# pc_afe44xx_shield_v2.net
KiCad netlist of a schematic drawn in EAGLE
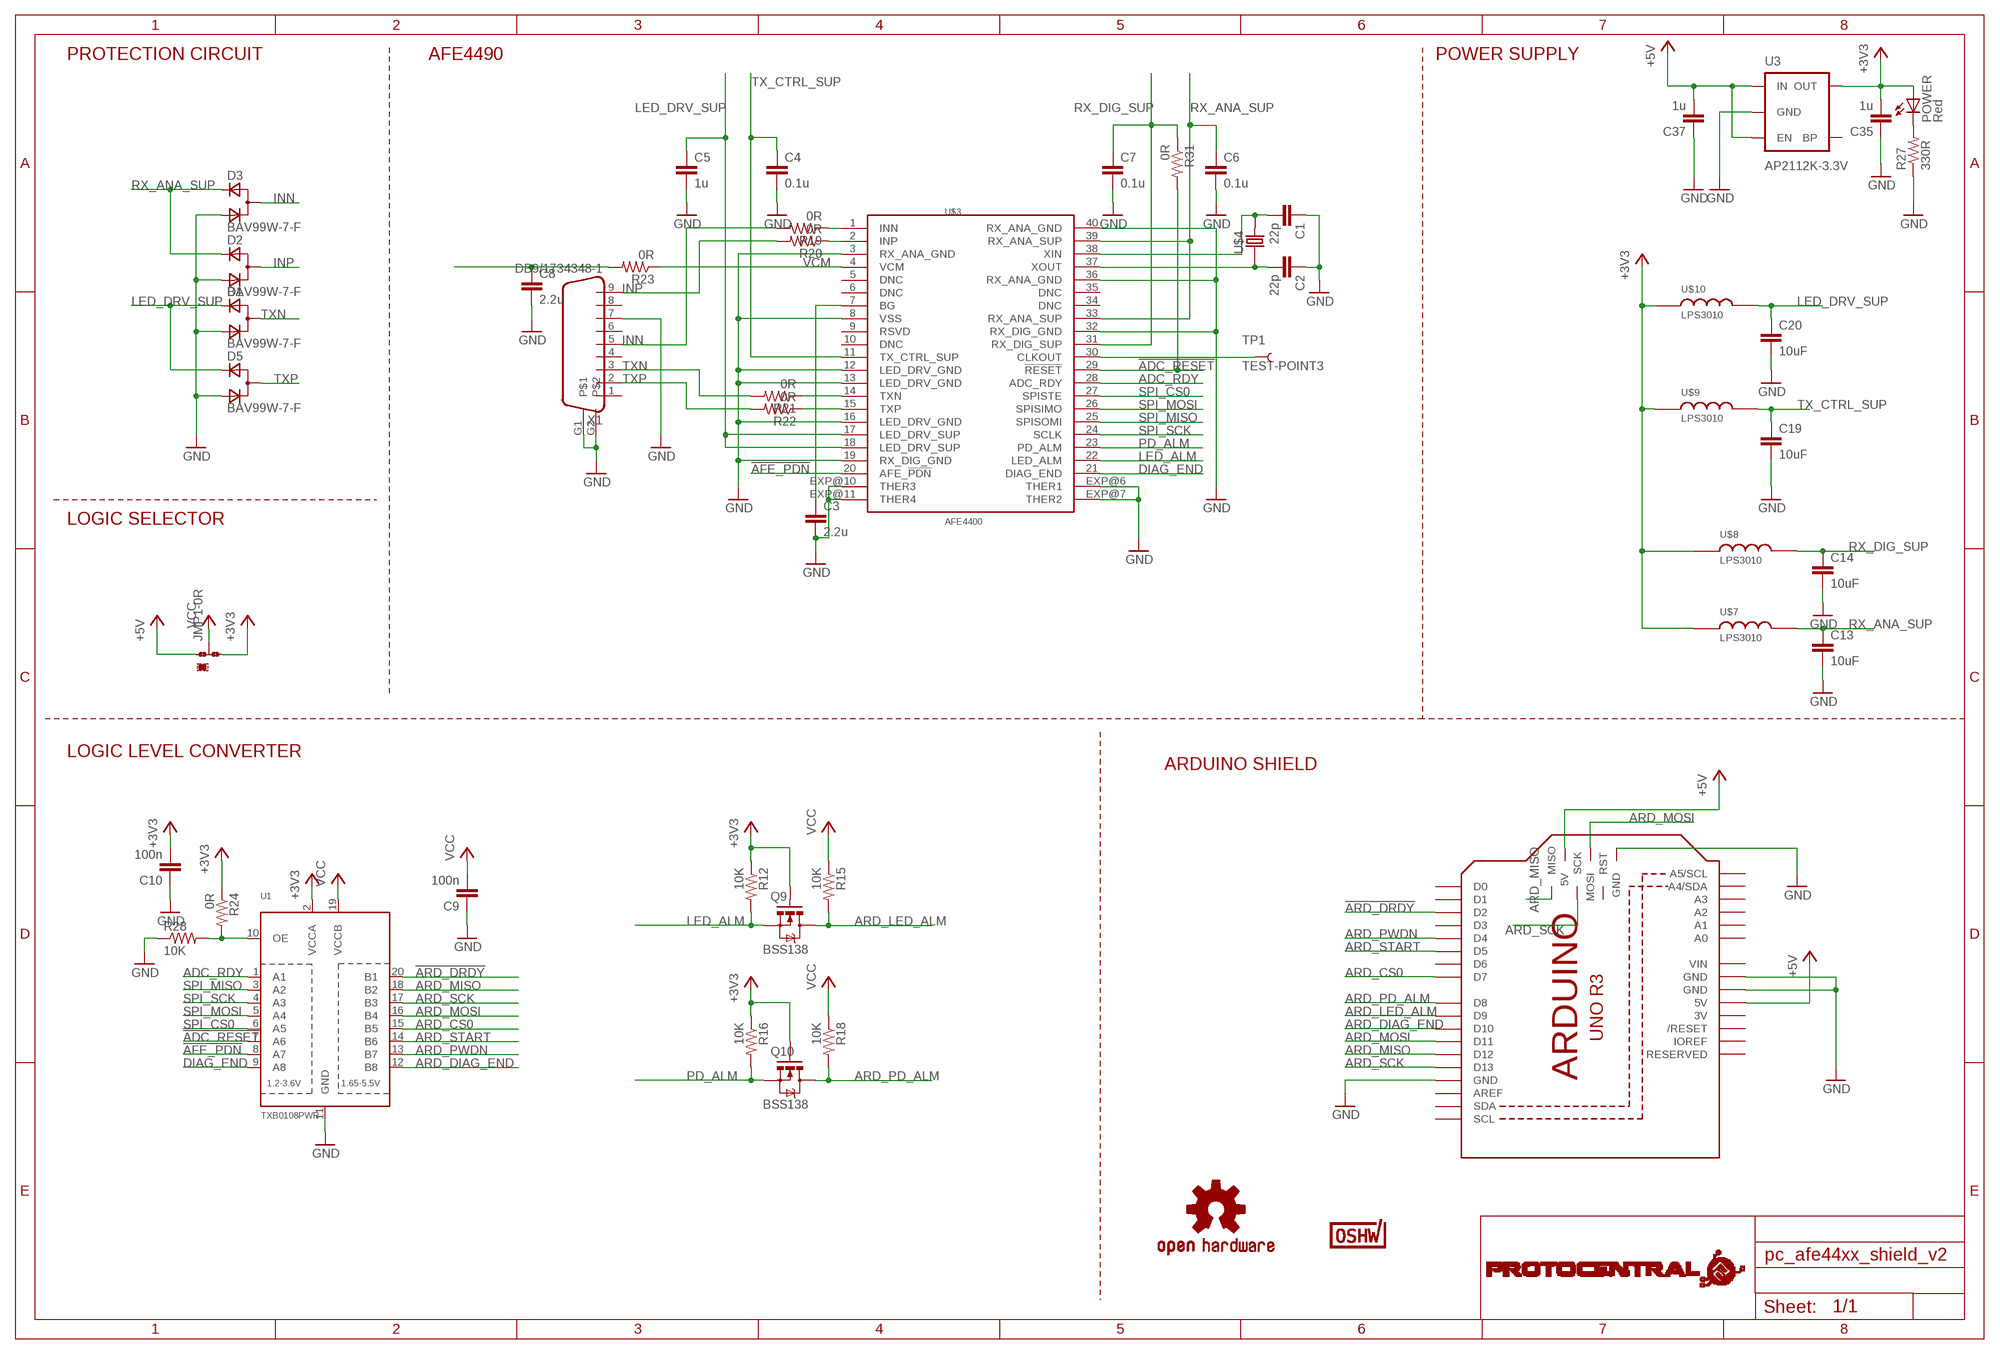
[diagram p0: schematic, sheet 1]

(export (version "E")
  (design (tool "Eeschema 10.0.6"))
  (components
    (comp (ref "C1")
      (value "22p")
      (footprint "eagle-import:C0402")
      (libsource (lib "eagle-import") (part "C-EUC0402"))
    )
    (comp (ref "C2")
      (value "22p")
      (footprint "eagle-import:C0402")
      (libsource (lib "eagle-import") (part "C-EUC0402"))
    )
    (comp (ref "C3")
      (value "2.2u")
      (footprint "eagle-import:C0402")
      (libsource (lib "eagle-import") (part "C-EUC0402"))
    )
    (comp (ref "C4")
      (value "0.1u")
      (footprint "eagle-import:C0805")
      (libsource (lib "eagle-import") (part "C-EUC0805"))
    )
    (comp (ref "C5")
      (value "1u")
      (footprint "eagle-import:C0805")
      (libsource (lib "eagle-import") (part "C-EUC0805"))
    )
    (comp (ref "C6")
      (value "0.1u")
      (footprint "eagle-import:C0805")
      (libsource (lib "eagle-import") (part "C-EUC0805"))
    )
    (comp (ref "C7")
      (value "0.1u")
      (footprint "eagle-import:C0805")
      (libsource (lib "eagle-import") (part "C-EUC0805"))
    )
    (comp (ref "C8")
      (value "2.2u")
      (footprint "eagle-import:C0402")
      (libsource (lib "eagle-import") (part "C-EUC0402"))
    )
    (comp (ref "C9")
      (value "100n")
      (footprint "eagle-import:C0402")
      (libsource (lib "eagle-import") (part "C-EUC0402"))
    )
    (comp (ref "C10")
      (value "100n")
      (footprint "eagle-import:C0402")
      (libsource (lib "eagle-import") (part "C-EUC0402"))
    )
    (comp (ref "C13")
      (value "10uF")
      (footprint "eagle-import:C0805")
      (libsource (lib "eagle-import") (part "C-EUC0805"))
    )
    (comp (ref "C14")
      (value "10uF")
      (footprint "eagle-import:C0805")
      (libsource (lib "eagle-import") (part "C-EUC0805"))
    )
    (comp (ref "C19")
      (value "10uF")
      (footprint "eagle-import:C0805")
      (libsource (lib "eagle-import") (part "C-EUC0805"))
    )
    (comp (ref "C20")
      (value "10uF")
      (footprint "eagle-import:C0805")
      (libsource (lib "eagle-import") (part "C-EUC0805"))
    )
    (comp (ref "C35")
      (value "1u")
      (footprint "eagle-import:C0805")
      (libsource (lib "eagle-import") (part "C-EUC0805"))
    )
    (comp (ref "C37")
      (value "1u")
      (footprint "eagle-import:C0805")
      (libsource (lib "eagle-import") (part "C-EUC0805"))
    )
    (comp (ref "D1")
      (value "BAV99W-7-F")
      (footprint "eagle-import:SOT323")
      (libsource (lib "eagle-import") (part "D_ACACSOT323"))
    )
    (comp (ref "D2")
      (value "BAV99W-7-F")
      (footprint "eagle-import:SOT323")
      (libsource (lib "eagle-import") (part "D_ACACSOT323"))
    )
    (comp (ref "D3")
      (value "BAV99W-7-F")
      (footprint "eagle-import:SOT323")
      (libsource (lib "eagle-import") (part "D_ACACSOT323"))
    )
    (comp (ref "D5")
      (value "BAV99W-7-F")
      (footprint "eagle-import:SOT323")
      (libsource (lib "eagle-import") (part "D_ACACSOT323"))
    )
    (comp (ref "JMP1")
      (value "0R-JUMPA")
      (footprint "eagle-import:A0R-JMP")
      (libsource (lib "eagle-import") (part "0R-JUMPA"))
    )
    (comp (ref "M1")
      (value "ARDUINO")
      (footprint "eagle-import:ARDUINO")
      (libsource (lib "eagle-import") (part "ARDUINO"))
    )
    (comp (ref "POWER")
      (value "Red")
      (footprint "eagle-import:CHIPLED_0603")
      (libsource (lib "eagle-import") (part "LEDCHIPLED_0603"))
    )
    (comp (ref "Q9")
      (value "BSS138")
      (footprint "eagle-import:SOT23-3")
      (libsource (lib "eagle-import") (part "MOSFET-NCHANNELSMD"))
    )
    (comp (ref "Q10")
      (value "BSS138")
      (footprint "eagle-import:SOT23-3")
      (libsource (lib "eagle-import") (part "MOSFET-NCHANNELSMD"))
    )
    (comp (ref "R12")
      (value "10K")
      (footprint "eagle-import:0805")
      (libsource (lib "eagle-import") (part "RESISTOR0805-RES"))
    )
    (comp (ref "R15")
      (value "10K")
      (footprint "eagle-import:0805")
      (libsource (lib "eagle-import") (part "RESISTOR0805-RES"))
    )
    (comp (ref "R16")
      (value "10K")
      (footprint "eagle-import:0805")
      (libsource (lib "eagle-import") (part "RESISTOR0805-RES"))
    )
    (comp (ref "R18")
      (value "10K")
      (footprint "eagle-import:0805")
      (libsource (lib "eagle-import") (part "RESISTOR0805-RES"))
    )
    (comp (ref "R19")
      (value "0R")
      (footprint "eagle-import:R0402")
      (libsource (lib "eagle-import") (part "R-US_R0402"))
    )
    (comp (ref "R20")
      (value "0R")
      (footprint "eagle-import:R0402")
      (libsource (lib "eagle-import") (part "R-US_R0402"))
    )
    (comp (ref "R21")
      (value "0R")
      (footprint "eagle-import:R0805")
      (libsource (lib "eagle-import") (part "R-US_R0805"))
    )
    (comp (ref "R22")
      (value "0R")
      (footprint "eagle-import:R0805")
      (libsource (lib "eagle-import") (part "R-US_R0805"))
    )
    (comp (ref "R23")
      (value "0R")
      (footprint "eagle-import:R0402")
      (libsource (lib "eagle-import") (part "R-US_R0402"))
    )
    (comp (ref "R24")
      (value "0R")
      (footprint "eagle-import:0805")
      (libsource (lib "eagle-import") (part "RESISTOR0805-RES"))
    )
    (comp (ref "R27")
      (value "330R")
      (footprint "eagle-import:R0805")
      (libsource (lib "eagle-import") (part "R-US_R0805"))
    )
    (comp (ref "R28")
      (value "10K")
      (footprint "eagle-import:0805")
      (libsource (lib "eagle-import") (part "RESISTOR0805-RES"))
    )
    (comp (ref "R31")
      (value "0R")
      (footprint "eagle-import:R0805")
      (libsource (lib "eagle-import") (part "R-US_R0805"))
    )
    (comp (ref "TP1")
      (value "TEST-POINT3")
      (footprint "eagle-import:PAD.03X.03")
      (libsource (lib "eagle-import") (part "TEST-POINT3"))
    )
    (comp (ref "U$3")
      (value "AFE4400")
      (footprint "eagle-import:QFN-40")
      (libsource (lib "eagle-import") (part "AFE4400"))
    )
    (comp (ref "U$4")
      (value "ABM3")
      (footprint "eagle-import:ABM3")
      (libsource (lib "eagle-import") (part "ABM3"))
    )
    (comp (ref "U$5")
      (value "PROTY_LOGO_WITH_TEXT")
      (footprint "eagle-import:PROTY_WITH_TEXT")
      (libsource (lib "eagle-import") (part "PROTY_LOGO_WITH_TEXT"))
    )
    (comp (ref "U$6")
      (value "CERT-SMALL")
      (footprint "eagle-import:CERT-SMALL-SILK")
      (libsource (lib "eagle-import") (part "CERT-SMALL"))
    )
    (comp (ref "U$7")
      (value "LPS3010")
      (footprint "eagle-import:LPS")
      (libsource (lib "eagle-import") (part "LPS"))
    )
    (comp (ref "U$8")
      (value "LPS3010")
      (footprint "eagle-import:LPS")
      (libsource (lib "eagle-import") (part "LPS"))
    )
    (comp (ref "U$9")
      (value "LPS3010")
      (footprint "eagle-import:LPS")
      (libsource (lib "eagle-import") (part "LPS"))
    )
    (comp (ref "U$10")
      (value "LPS3010")
      (footprint "eagle-import:LPS")
      (libsource (lib "eagle-import") (part "LPS"))
    )
    (comp (ref "U$11")
      (value "OSHW-LOGOM")
      (footprint "eagle-import:OSHW-LOGO-M")
      (libsource (lib "eagle-import") (part "OSHW-LOGOM"))
    )
    (comp (ref "U1")
      (value "TXB0108PWR")
      (footprint "eagle-import:TSSOP20")
      (libsource (lib "eagle-import") (part "TXB0108PWR"))
    )
    (comp (ref "U3")
      (value "AP2112K-3.3V")
      (footprint "eagle-import:SOT23-5")
      (libsource (lib "eagle-import") (part "V_REG_LDOSMD"))
    )
    (comp (ref "X1")
      (value "DB9/1734348-1")
      (footprint "eagle-import:DB9")
      (libsource (lib "eagle-import") (part "DB9"))
    )
  )
  (nets
    (net (code "1") (name "+3V3") (class "Default")
      (node (ref "C10") (pin "2") (pinfunction "2_2") (pintype "passive"))
      (node (ref "C35") (pin "2") (pinfunction "2_2") (pintype "passive"))
      (node (ref "JMP1") (pin "3") (pinfunction "3_3") (pintype "passive"))
      (node (ref "POWER") (pin "A") (pinfunction "A_A") (pintype "passive"))
      (node (ref "Q10") (pin "1") (pinfunction "G_1") (pintype "passive"))
      (node (ref "Q9") (pin "1") (pinfunction "G_1") (pintype "passive"))
      (node (ref "R12") (pin "1") (pinfunction "1_1") (pintype "passive"))
      (node (ref "R16") (pin "1") (pinfunction "1_1") (pintype "passive"))
      (node (ref "R24") (pin "1") (pinfunction "1_1") (pintype "passive"))
      (node (ref "U$10") (pin "1") (pinfunction "P$1_1") (pintype "bidirectional"))
      (node (ref "U$7") (pin "1") (pinfunction "P$1_1") (pintype "bidirectional"))
      (node (ref "U$8") (pin "1") (pinfunction "P$1_1") (pintype "bidirectional"))
      (node (ref "U$9") (pin "1") (pinfunction "P$1_1") (pintype "bidirectional"))
      (node (ref "U1") (pin "2") (pinfunction "VCCA_2") (pintype "bidirectional"))
      (node (ref "U3") (pin "5") (pinfunction "OUT_5") (pintype "passive"))
    )
    (net (code "2") (name "+5V") (class "Default")
      (node (ref "C37") (pin "2") (pinfunction "2_2") (pintype "passive"))
      (node (ref "JMP1") (pin "1") (pinfunction "1_1") (pintype "passive"))
      (node (ref "M1") (pin "5V") (pinfunction "5V_5V") (pintype "power_in"))
      (node (ref "M1") (pin "5V_ICSP") (pinfunction "5V_5V_ICSP") (pintype "passive"))
      (node (ref "U3") (pin "1") (pinfunction "IN_1") (pintype "input"))
      (node (ref "U3") (pin "3") (pinfunction "EN_3") (pintype "input"))
    )
    (net (code "3") (name "/3V") (class "Default")
      (node (ref "M1") (pin "3V") (pinfunction "3V_3V") (pintype "power_in"))
    )
    (net (code "4") (name "/ADC_RDY") (class "Default")
      (node (ref "U$3") (pin "28") (pinfunction "ADC_RDY_28") (pintype "bidirectional"))
      (node (ref "U1") (pin "1") (pinfunction "A1_1") (pintype "bidirectional"))
    )
    (net (code "5") (name "/ARD_CS0") (class "Default")
      (node (ref "M1") (pin "D7") (pinfunction "D7_D7") (pintype "bidirectional"))
      (node (ref "U1") (pin "15") (pinfunction "B5_15") (pintype "bidirectional"))
    )
    (net (code "6") (name "/ARD_DIAG_END") (class "Default")
      (node (ref "M1") (pin "D10") (pinfunction "D10_D10") (pintype "bidirectional"))
      (node (ref "U1") (pin "12") (pinfunction "B8_12") (pintype "bidirectional"))
    )
    (net (code "7") (name "/ARD_LED_ALM") (class "Default")
      (node (ref "M1") (pin "D9") (pinfunction "D9_D9") (pintype "bidirectional"))
      (node (ref "Q9") (pin "3") (pinfunction "D_3") (pintype "passive"))
      (node (ref "R15") (pin "2") (pinfunction "2_2") (pintype "passive"))
    )
    (net (code "8") (name "/ARD_MISO") (class "Default")
      (node (ref "M1") (pin "D12") (pinfunction "D12_D12") (pintype "bidirectional"))
      (node (ref "M1") (pin "MISO") (pinfunction "MISO_MISO") (pintype "passive"))
      (node (ref "U1") (pin "18") (pinfunction "B2_18") (pintype "bidirectional"))
    )
    (net (code "9") (name "/ARD_MOSI") (class "Default")
      (node (ref "M1") (pin "D11") (pinfunction "D11_D11") (pintype "bidirectional"))
      (node (ref "M1") (pin "MOSI") (pinfunction "MOSI_MOSI") (pintype "passive"))
      (node (ref "U1") (pin "16") (pinfunction "B4_16") (pintype "bidirectional"))
    )
    (net (code "10") (name "/ARD_PD_ALM") (class "Default")
      (node (ref "M1") (pin "D8") (pinfunction "D8_D8") (pintype "bidirectional"))
      (node (ref "Q10") (pin "3") (pinfunction "D_3") (pintype "passive"))
      (node (ref "R18") (pin "2") (pinfunction "2_2") (pintype "passive"))
    )
    (net (code "11") (name "/ARD_PWDN") (class "Default")
      (node (ref "M1") (pin "D4") (pinfunction "D4_D4") (pintype "bidirectional"))
      (node (ref "U1") (pin "13") (pinfunction "B7_13") (pintype "bidirectional"))
    )
    (net (code "12") (name "/ARD_SCK") (class "Default")
      (node (ref "M1") (pin "D13") (pinfunction "D13_D13") (pintype "bidirectional"))
      (node (ref "M1") (pin "SCK") (pinfunction "SCK_SCK") (pintype "passive"))
      (node (ref "U1") (pin "17") (pinfunction "B3_17") (pintype "bidirectional"))
    )
    (net (code "13") (name "/ARD_START") (class "Default")
      (node (ref "M1") (pin "D5") (pinfunction "D5_D5") (pintype "bidirectional"))
      (node (ref "U1") (pin "14") (pinfunction "B6_14") (pintype "bidirectional"))
    )
    (net (code "14") (name "/DIAG_END") (class "Default")
      (node (ref "U$3") (pin "21") (pinfunction "DIAG_END_21") (pintype "bidirectional"))
      (node (ref "U1") (pin "9") (pinfunction "A8_9") (pintype "bidirectional"))
    )
    (net (code "15") (name "/INN") (class "Default")
      (node (ref "D3") (pin "1") (pinfunction "CA_1") (pintype "passive"))
      (node (ref "R19") (pin "2") (pinfunction "2_2") (pintype "passive"))
      (node (ref "X1") (pin "5") (pinfunction "5_5") (pintype "passive"))
    )
    (net (code "16") (name "/INP") (class "Default")
      (node (ref "D2") (pin "1") (pinfunction "CA_1") (pintype "passive"))
      (node (ref "R20") (pin "2") (pinfunction "2_2") (pintype "passive"))
      (node (ref "X1") (pin "9") (pinfunction "9_9") (pintype "passive"))
    )
    (net (code "17") (name "/LED_ALM") (class "Default")
      (node (ref "Q9") (pin "2") (pinfunction "S_2") (pintype "passive"))
      (node (ref "R12") (pin "2") (pinfunction "2_2") (pintype "passive"))
      (node (ref "U$3") (pin "22") (pinfunction "LED_ALM_22") (pintype "bidirectional"))
    )
    (net (code "18") (name "/LED_DRV_SUP") (class "Default")
      (node (ref "C20") (pin "1") (pinfunction "1_1") (pintype "passive"))
      (node (ref "C5") (pin "1") (pinfunction "1_1") (pintype "passive"))
      (node (ref "D1") (pin "3") (pinfunction "A_3") (pintype "passive"))
      (node (ref "D5") (pin "3") (pinfunction "A_3") (pintype "passive"))
      (node (ref "U$10") (pin "2") (pinfunction "P$2_2") (pintype "bidirectional"))
      (node (ref "U$3") (pin "17") (pinfunction "LED_DRV_SUP_17") (pintype "bidirectional"))
      (node (ref "U$3") (pin "18") (pinfunction "LED_DRV_SUP_18") (pintype "bidirectional"))
    )
    (net (code "19") (name "/PD_ALM") (class "Default")
      (node (ref "Q10") (pin "2") (pinfunction "S_2") (pintype "passive"))
      (node (ref "R16") (pin "2") (pinfunction "2_2") (pintype "passive"))
      (node (ref "U$3") (pin "23") (pinfunction "PD_ALM_23") (pintype "bidirectional"))
    )
    (net (code "20") (name "/RX_ANA_SUP") (class "Default")
      (node (ref "C13") (pin "1") (pinfunction "1_1") (pintype "passive"))
      (node (ref "C6") (pin "1") (pinfunction "1_1") (pintype "passive"))
      (node (ref "D2") (pin "3") (pinfunction "A_3") (pintype "passive"))
      (node (ref "D3") (pin "3") (pinfunction "A_3") (pintype "passive"))
      (node (ref "U$3") (pin "33") (pinfunction "RX_ANA_SUP_33") (pintype "bidirectional"))
      (node (ref "U$3") (pin "39") (pinfunction "RX_ANA_SUP_39") (pintype "bidirectional"))
      (node (ref "U$7") (pin "2") (pinfunction "P$2_2") (pintype "bidirectional"))
    )
    (net (code "21") (name "/RX_DIG_SUP") (class "Default")
      (node (ref "C14") (pin "1") (pinfunction "1_1") (pintype "passive"))
      (node (ref "C7") (pin "1") (pinfunction "1_1") (pintype "passive"))
      (node (ref "R31") (pin "1") (pinfunction "1_1") (pintype "passive"))
      (node (ref "U$3") (pin "31") (pinfunction "RX_DIG_SUP_31") (pintype "bidirectional"))
      (node (ref "U$8") (pin "2") (pinfunction "P$2_2") (pintype "bidirectional"))
    )
    (net (code "22") (name "/SPI_CS0") (class "Default")
      (node (ref "U$3") (pin "27") (pinfunction "SPISTE_27") (pintype "bidirectional"))
      (node (ref "U1") (pin "6") (pinfunction "A5_6") (pintype "bidirectional"))
    )
    (net (code "23") (name "/SPI_MISO") (class "Default")
      (node (ref "U$3") (pin "25") (pinfunction "SPISOMI_25") (pintype "bidirectional"))
      (node (ref "U1") (pin "3") (pinfunction "A2_3") (pintype "bidirectional"))
    )
    (net (code "24") (name "/SPI_MOSI") (class "Default")
      (node (ref "U$3") (pin "26") (pinfunction "SPISIMO_26") (pintype "bidirectional"))
      (node (ref "U1") (pin "5") (pinfunction "A4_5") (pintype "bidirectional"))
    )
    (net (code "25") (name "/SPI_SCK") (class "Default")
      (node (ref "U$3") (pin "24") (pinfunction "SCLK_24") (pintype "bidirectional"))
      (node (ref "U1") (pin "4") (pinfunction "A3_4") (pintype "bidirectional"))
    )
    (net (code "26") (name "/TXN") (class "Default")
      (node (ref "D1") (pin "1") (pinfunction "CA_1") (pintype "passive"))
      (node (ref "R21") (pin "2") (pinfunction "2_2") (pintype "passive"))
      (node (ref "X1") (pin "3") (pinfunction "3_3") (pintype "passive"))
    )
    (net (code "27") (name "/TXP") (class "Default")
      (node (ref "D5") (pin "1") (pinfunction "CA_1") (pintype "passive"))
      (node (ref "R22") (pin "2") (pinfunction "2_2") (pintype "passive"))
      (node (ref "X1") (pin "2") (pinfunction "2_2") (pintype "passive"))
    )
    (net (code "28") (name "/TX_CTRL_SUP") (class "Default")
      (node (ref "C19") (pin "1") (pinfunction "1_1") (pintype "passive"))
      (node (ref "C4") (pin "1") (pinfunction "1_1") (pintype "passive"))
      (node (ref "U$3") (pin "11") (pinfunction "TX_CTRL_SUP_11") (pintype "bidirectional"))
      (node (ref "U$9") (pin "2") (pinfunction "P$2_2") (pintype "bidirectional"))
    )
    (net (code "29") (name "/VCM") (class "Default")
      (node (ref "R23") (pin "1") (pinfunction "1_1") (pintype "passive"))
      (node (ref "U$3") (pin "4") (pinfunction "VCM_4") (pintype "bidirectional"))
    )
    (net (code "30") (name "/VIN") (class "Default")
      (node (ref "M1") (pin "VIN") (pinfunction "VIN_VIN") (pintype "power_in"))
    )
    (net (code "31") (name "/~{ADC_RESET}") (class "Default")
      (node (ref "R31") (pin "2") (pinfunction "2_2") (pintype "passive"))
      (node (ref "U$3") (pin "29") (pinfunction "~{RESET}_29") (pintype "bidirectional"))
      (node (ref "U1") (pin "7") (pinfunction "A6_7") (pintype "bidirectional"))
    )
    (net (code "32") (name "/~{AFE_PDN}") (class "Default")
      (node (ref "U$3") (pin "20") (pinfunction "AFE_~{PDN}_20") (pintype "bidirectional"))
      (node (ref "U1") (pin "8") (pinfunction "A7_8") (pintype "bidirectional"))
    )
    (net (code "33") (name "/~{ARD_DRDY}") (class "Default")
      (node (ref "M1") (pin "D2") (pinfunction "D2_D2") (pintype "bidirectional"))
      (node (ref "U1") (pin "20") (pinfunction "B1_20") (pintype "bidirectional"))
    )
    (net (code "34") (name "GND") (class "Default")
      (node (ref "C1") (pin "1") (pinfunction "1_1") (pintype "passive"))
      (node (ref "C10") (pin "1") (pinfunction "1_1") (pintype "passive"))
      (node (ref "C13") (pin "2") (pinfunction "2_2") (pintype "passive"))
      (node (ref "C14") (pin "2") (pinfunction "2_2") (pintype "passive"))
      (node (ref "C19") (pin "2") (pinfunction "2_2") (pintype "passive"))
      (node (ref "C2") (pin "1") (pinfunction "1_1") (pintype "passive"))
      (node (ref "C20") (pin "2") (pinfunction "2_2") (pintype "passive"))
      (node (ref "C3") (pin "2") (pinfunction "2_2") (pintype "passive"))
      (node (ref "C35") (pin "1") (pinfunction "1_1") (pintype "passive"))
      (node (ref "C37") (pin "1") (pinfunction "1_1") (pintype "passive"))
      (node (ref "C4") (pin "2") (pinfunction "2_2") (pintype "passive"))
      (node (ref "C5") (pin "2") (pinfunction "2_2") (pintype "passive"))
      (node (ref "C6") (pin "2") (pinfunction "2_2") (pintype "passive"))
      (node (ref "C7") (pin "2") (pinfunction "2_2") (pintype "passive"))
      (node (ref "C8") (pin "2") (pinfunction "2_2") (pintype "passive"))
      (node (ref "C9") (pin "1") (pinfunction "1_1") (pintype "passive"))
      (node (ref "D1") (pin "2") (pinfunction "C_2") (pintype "passive"))
      (node (ref "D2") (pin "2") (pinfunction "C_2") (pintype "passive"))
      (node (ref "D3") (pin "2") (pinfunction "C_2") (pintype "passive"))
      (node (ref "D5") (pin "2") (pinfunction "C_2") (pintype "passive"))
      (node (ref "M1") (pin "GND") (pinfunction "GND_GND") (pintype "power_in"))
      (node (ref "M1") (pin "GND@1") (pinfunction "GND_GND@1") (pintype "power_in"))
      (node (ref "M1") (pin "GND@2") (pinfunction "GND_GND@2") (pintype "power_in"))
      (node (ref "M1") (pin "GND@3") (pinfunction "GND_GND@3") (pintype "passive"))
      (node (ref "R27") (pin "1") (pinfunction "1_1") (pintype "passive"))
      (node (ref "R28") (pin "1") (pinfunction "1_1") (pintype "passive"))
      (node (ref "U$3") (pin "12") (pinfunction "LED_DRV_GND_12") (pintype "bidirectional"))
      (node (ref "U$3") (pin "13") (pinfunction "LED_DRV_GND_13") (pintype "bidirectional"))
      (node (ref "U$3") (pin "16") (pinfunction "LED_DRV_GND_16") (pintype "bidirectional"))
      (node (ref "U$3") (pin "19") (pinfunction "RX_DIG_GND_19") (pintype "bidirectional"))
      (node (ref "U$3") (pin "3") (pinfunction "RX_ANA_GND_3") (pintype "bidirectional"))
      (node (ref "U$3") (pin "32") (pinfunction "RX_DIG_GND_32") (pintype "bidirectional"))
      (node (ref "U$3") (pin "36") (pinfunction "RX_ANA_GND_36") (pintype "bidirectional"))
      (node (ref "U$3") (pin "40") (pinfunction "RX_ANA_GND_40") (pintype "bidirectional"))
      (node (ref "U$3") (pin "8") (pinfunction "VSS_8") (pintype "bidirectional"))
      (node (ref "U$3") (pin "EXP@10") (pinfunction "THER3_EXP@10") (pintype "bidirectional"))
      (node (ref "U$3") (pin "EXP@11") (pinfunction "THER4_EXP@11") (pintype "bidirectional"))
      (node (ref "U$3") (pin "EXP@6") (pinfunction "THER1_EXP@6") (pintype "bidirectional"))
      (node (ref "U$3") (pin "EXP@7") (pinfunction "THER2_EXP@7") (pintype "bidirectional"))
      (node (ref "U1") (pin "11") (pinfunction "GND_11") (pintype "bidirectional"))
      (node (ref "U3") (pin "2") (pinfunction "GND_2") (pintype "input"))
      (node (ref "X1") (pin "7") (pinfunction "7_7") (pintype "passive"))
      (node (ref "X1") (pin "G1") (pinfunction "P$1_G1") (pintype "bidirectional"))
      (node (ref "X1") (pin "G2") (pinfunction "P$2_G2") (pintype "bidirectional"))
    )
    (net (code "35") (name "Net-(C8-Pad1)") (class "Default")
      (node (ref "C8") (pin "1") (pinfunction "1_1") (pintype "passive"))
      (node (ref "R23") (pin "2") (pinfunction "2_2") (pintype "passive"))
    )
    (net (code "36") (name "Net-(POWER-PadC)") (class "Default")
      (node (ref "POWER") (pin "C") (pinfunction "C_C") (pintype "passive"))
      (node (ref "R27") (pin "2") (pinfunction "2_2") (pintype "passive"))
    )
    (net (code "37") (name "Net-(TP1-1)") (class "Default")
      (node (ref "TP1") (pin "P$1") (pinfunction "1_P$1") (pintype "bidirectional"))
      (node (ref "U$3") (pin "30") (pinfunction "CLKOUT_30") (pintype "bidirectional"))
    )
    (net (code "38") (name "Net-(U$3-BG)") (class "Default")
      (node (ref "C3") (pin "1") (pinfunction "1_1") (pintype "passive"))
      (node (ref "U$3") (pin "7") (pinfunction "BG_7") (pintype "bidirectional"))
    )
    (net (code "39") (name "Net-(U$3-INN)") (class "Default")
      (node (ref "R19") (pin "1") (pinfunction "1_1") (pintype "passive"))
      (node (ref "U$3") (pin "1") (pinfunction "INN_1") (pintype "bidirectional"))
    )
    (net (code "40") (name "Net-(U$3-INP)") (class "Default")
      (node (ref "R20") (pin "1") (pinfunction "1_1") (pintype "passive"))
      (node (ref "U$3") (pin "2") (pinfunction "INP_2") (pintype "bidirectional"))
    )
    (net (code "41") (name "Net-(U$3-TXN)") (class "Default")
      (node (ref "R21") (pin "1") (pinfunction "1_1") (pintype "passive"))
      (node (ref "U$3") (pin "14") (pinfunction "TXN_14") (pintype "bidirectional"))
    )
    (net (code "42") (name "Net-(U$3-TXP)") (class "Default")
      (node (ref "R22") (pin "1") (pinfunction "1_1") (pintype "passive"))
      (node (ref "U$3") (pin "15") (pinfunction "TXP_15") (pintype "bidirectional"))
    )
    (net (code "43") (name "Net-(U$3-XIN)") (class "Default")
      (node (ref "C1") (pin "2") (pinfunction "2_2") (pintype "passive"))
      (node (ref "U$3") (pin "38") (pinfunction "XIN_38") (pintype "bidirectional"))
      (node (ref "U$4") (pin "2") (pinfunction "2_2") (pintype "passive"))
    )
    (net (code "44") (name "Net-(U$3-XOUT)") (class "Default")
      (node (ref "C2") (pin "2") (pinfunction "2_2") (pintype "passive"))
      (node (ref "U$3") (pin "37") (pinfunction "XOUT_37") (pintype "bidirectional"))
      (node (ref "U$4") (pin "1") (pinfunction "1_1") (pintype "passive"))
    )
    (net (code "45") (name "Net-(U1-OE)") (class "Default")
      (node (ref "R24") (pin "2") (pinfunction "2_2") (pintype "passive"))
      (node (ref "R28") (pin "2") (pinfunction "2_2") (pintype "passive"))
      (node (ref "U1") (pin "10") (pinfunction "OE_10") (pintype "bidirectional"))
    )
    (net (code "46") (name "VCC") (class "Default")
      (node (ref "C9") (pin "2") (pinfunction "2_2") (pintype "passive"))
      (node (ref "JMP1") (pin "2") (pinfunction "2_2") (pintype "passive"))
      (node (ref "R15") (pin "1") (pinfunction "1_1") (pintype "passive"))
      (node (ref "R18") (pin "1") (pinfunction "1_1") (pintype "passive"))
      (node (ref "U1") (pin "19") (pinfunction "VCCB_19") (pintype "bidirectional"))
    )
    (net (code "47") (name "unconnected-(M1-A4{slash}SDA-PadA4)") (class "Default")
      (node (ref "M1") (pin "A4") (pinfunction "A4/SDA_A4") (pintype "bidirectional"))
    )
    (net (code "48") (name "unconnected-(M1-A5{slash}SCL-PadA5)") (class "Default")
      (node (ref "M1") (pin "A5") (pinfunction "A5/SCL_A5") (pintype "bidirectional"))
    )
    (net (code "49") (name "unconnected-(M1-PadA0)") (class "Default")
      (node (ref "M1") (pin "A0") (pinfunction "A0_A0") (pintype "bidirectional"))
    )
    (net (code "50") (name "unconnected-(M1-PadA1)") (class "Default")
      (node (ref "M1") (pin "A1") (pinfunction "A1_A1") (pintype "bidirectional"))
    )
    (net (code "51") (name "unconnected-(M1-PadA2)") (class "Default")
      (node (ref "M1") (pin "A2") (pinfunction "A2_A2") (pintype "bidirectional"))
    )
    (net (code "52") (name "unconnected-(M1-PadA3)") (class "Default")
      (node (ref "M1") (pin "A3") (pinfunction "A3_A3") (pintype "bidirectional"))
    )
    (net (code "53") (name "unconnected-(M1-PadAREF)") (class "Default")
      (node (ref "M1") (pin "AREF") (pinfunction "AREF_AREF") (pintype "bidirectional"))
    )
    (net (code "54") (name "unconnected-(M1-PadD0)") (class "Default")
      (node (ref "M1") (pin "D0") (pinfunction "D0_D0") (pintype "bidirectional"))
    )
    (net (code "55") (name "unconnected-(M1-PadD1)") (class "Default")
      (node (ref "M1") (pin "D1") (pinfunction "D1_D1") (pintype "bidirectional"))
    )
    (net (code "56") (name "unconnected-(M1-PadD3)") (class "Default")
      (node (ref "M1") (pin "D3") (pinfunction "D3_D3") (pintype "bidirectional"))
    )
    (net (code "57") (name "unconnected-(M1-PadD6)") (class "Default")
      (node (ref "M1") (pin "D6") (pinfunction "D6_D6") (pintype "bidirectional"))
    )
    (net (code "58") (name "unconnected-(M1-PadIOREF)") (class "Default")
      (node (ref "M1") (pin "IOREF") (pinfunction "IOREF_IOREF") (pintype "output"))
    )
    (net (code "59") (name "unconnected-(M1-PadRESERVED)") (class "Default")
      (node (ref "M1") (pin "RESERVED") (pinfunction "RESERVED_RESERVED") (pintype "no_connect"))
    )
    (net (code "60") (name "unconnected-(M1-PadSCL)") (class "Default")
      (node (ref "M1") (pin "SCL") (pinfunction "SCL_SCL") (pintype "bidirectional"))
    )
    (net (code "61") (name "unconnected-(M1-PadSDA)") (class "Default")
      (node (ref "M1") (pin "SDA") (pinfunction "SDA_SDA") (pintype "bidirectional"))
    )
    (net (code "62") (name "unconnected-(M1-RST-PadRESET_ICSP)") (class "Default")
      (node (ref "M1") (pin "RESET_ICSP") (pinfunction "RST_RESET_ICSP") (pintype "passive"))
    )
    (net (code "63") (name "unconnected-(M1-{slash}RESET-PadRESET)") (class "Default")
      (node (ref "M1") (pin "RESET") (pinfunction "/RESET_RESET") (pintype "bidirectional"))
    )
    (net (code "64") (name "unconnected-(U$3-DNC-Pad5)") (class "Default")
      (node (ref "U$3") (pin "5") (pinfunction "DNC_5") (pintype "bidirectional"))
    )
    (net (code "65") (name "unconnected-(U$3-DNC-Pad6)") (class "Default")
      (node (ref "U$3") (pin "6") (pinfunction "DNC_6") (pintype "bidirectional"))
    )
    (net (code "66") (name "unconnected-(U$3-DNC-Pad10)") (class "Default")
      (node (ref "U$3") (pin "10") (pinfunction "DNC_10") (pintype "bidirectional"))
    )
    (net (code "67") (name "unconnected-(U$3-DNC-Pad34)") (class "Default")
      (node (ref "U$3") (pin "34") (pinfunction "DNC_34") (pintype "bidirectional"))
    )
    (net (code "68") (name "unconnected-(U$3-DNC-Pad35)") (class "Default")
      (node (ref "U$3") (pin "35") (pinfunction "DNC_35") (pintype "bidirectional"))
    )
    (net (code "69") (name "unconnected-(U$3-RSVD-Pad9)") (class "Default")
      (node (ref "U$3") (pin "9") (pinfunction "RSVD_9") (pintype "bidirectional"))
    )
    (net (code "70") (name "unconnected-(U3-BP-Pad4)") (class "Default")
      (node (ref "U3") (pin "4") (pinfunction "BP_4") (pintype "input"))
    )
    (net (code "71") (name "unconnected-(X1-Pad1)") (class "Default")
      (node (ref "X1") (pin "1") (pinfunction "1_1") (pintype "passive"))
    )
    (net (code "72") (name "unconnected-(X1-Pad4)") (class "Default")
      (node (ref "X1") (pin "4") (pinfunction "4_4") (pintype "passive"))
    )
    (net (code "73") (name "unconnected-(X1-Pad6)") (class "Default")
      (node (ref "X1") (pin "6") (pinfunction "6_6") (pintype "passive"))
    )
    (net (code "74") (name "unconnected-(X1-Pad8)") (class "Default")
      (node (ref "X1") (pin "8") (pinfunction "8_8") (pintype "passive"))
    )
  )
)
